# Sch_front.net
KiCad netlist of a schematic drawn in Altium Designer
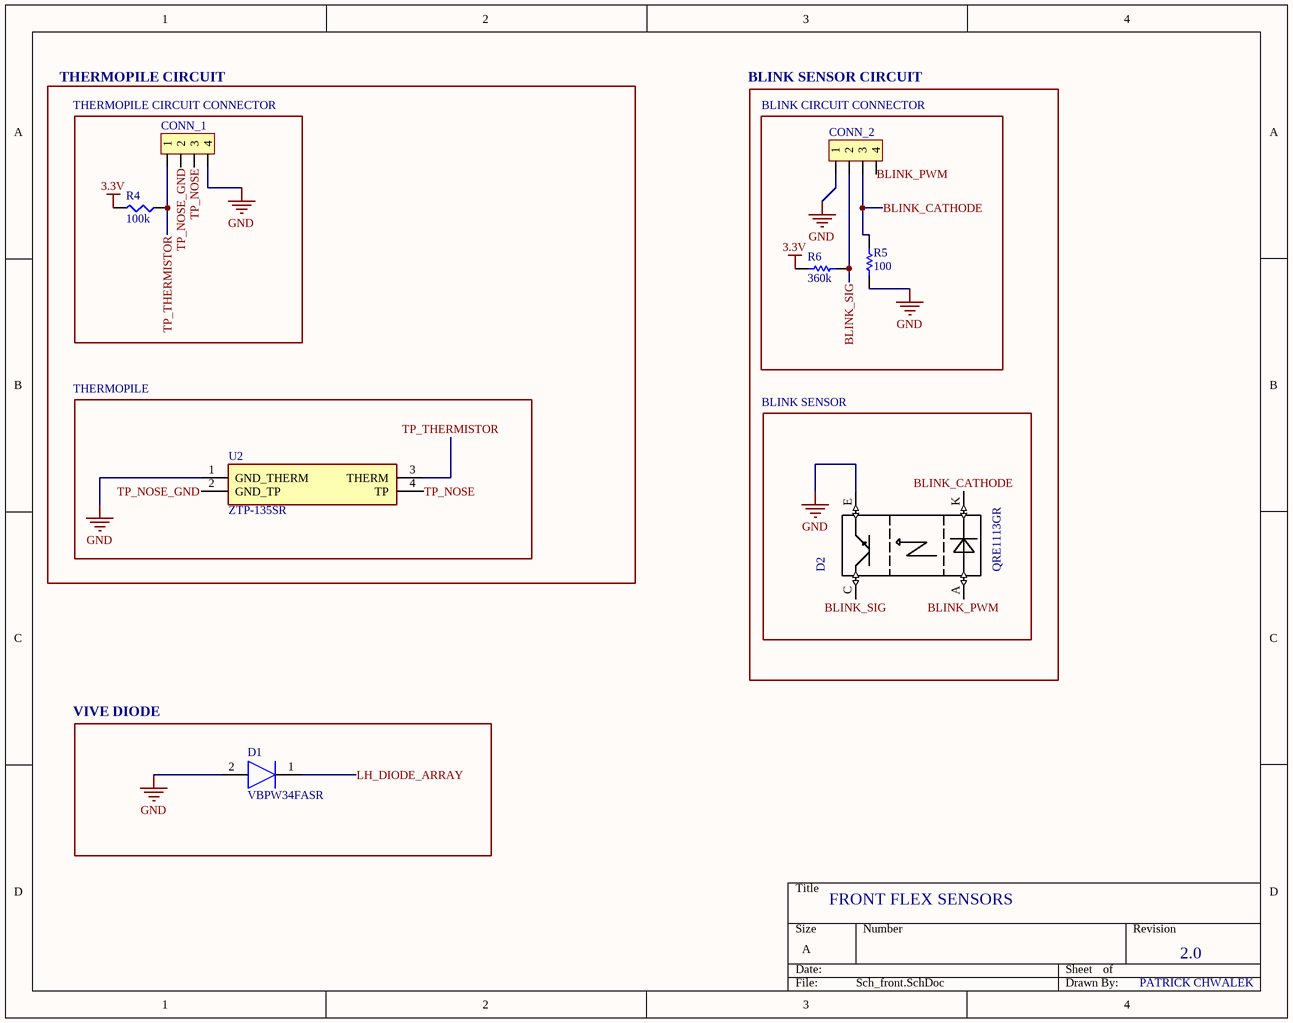
[diagram p0: Sch_front.SchDoc]

(export (version "E")
  (design (tool "Eeschema 10.0.6"))
  (components
    (comp (ref "CONN_1")
      (value "THERMO")
      (footprint "4_pos_1mm_header")
      (libsource (lib "schematic_components") (part "4_pin_1mm_header"))
    )
    (comp (ref "CONN_2")
      (value "BLINK")
      (footprint "4_pos_1mm_header")
      (libsource (lib "schematic_components") (part "4_pin_1mm_header"))
    )
    (comp (ref "D1")
      (value "VBPW34FASR")
      (footprint "VBPW34FAS")
      (description "Diode")
      (fields (field (name "MOUSER PART NUMBER") "782-VBPW34FASR") (field (name "RS PART NUMBER") "7689401"))
      (libsource (lib "*") (part "VBPW34FASR"))
    )
    (comp (ref "D2")
      (value "QRE1113GR")
      (footprint "*4LEADSMD_QRE1113GR(Primary)")
      (description "QRE1113 Series 30 V 50 mA Miniature Reflective Object Sensor - SMD-4")
      (fields (field (name "MF") "ON Semiconductor"))
      (libsource (lib "QRE1113GR") (part "QRE1113GR"))
    )
    (comp (ref "R4")
      (value "100k")
      (footprint "SMD-0402-RES")
      (description "RES SMD 100K OHM 5% 1/10W 0402")
      (fields (field (name "PART NUMBER") "ERJ-2GEJ104X") (field (name "DIGI-KEY PART NUMBER") "P100KJCT-ND"))
      (libsource (lib "Panasonic_ERJ_0402") (part "ERJ-2GEJ104X"))
    )
    (comp (ref "R5") (value "100") (footprint "0402R") (libsource (lib "bdm") (part "Resistor")))
    (comp (ref "R6")
      (value "360k")
      (footprint "0402R")
      (description "RC0402FR-07360KL")
      (libsource (lib "bdm") (part "Resistor"))
    )
    (comp (ref "U2")
      (value "ZTP-135SR")
      (footprint "ZTP-135SR")
      (description "Undefined or Miscellaneous")
      (fields (field (name "MOUSER PART NUMBER") "527-ZTP-135SR"))
      (libsource (lib "SamacSys") (part "ZTP-135SR"))
    )
  )
  (nets
    (net (code "1") (name "/BLINK_CATHODE") (class "Default")
      (node (ref "CONN_2") (pin "3") (pinfunction "3_3") (pintype "passive"))
      (node (ref "D2") (pin "K") (pinfunction "K_K") (pintype "bidirectional"))
      (node (ref "R5") (pin "2") (pinfunction "2_2") (pintype "passive"))
    )
    (net (code "2") (name "/BLINK_PWM") (class "Default")
      (node (ref "CONN_2") (pin "4") (pinfunction "4_4") (pintype "passive"))
      (node (ref "D2") (pin "A") (pinfunction "A_A") (pintype "bidirectional"))
    )
    (net (code "3") (name "/BLINK_SIG") (class "Default")
      (node (ref "CONN_2") (pin "2") (pinfunction "2_2") (pintype "passive"))
      (node (ref "D2") (pin "C") (pinfunction "C_C") (pintype "bidirectional"))
      (node (ref "R6") (pin "1") (pinfunction "1_1") (pintype "passive"))
    )
    (net (code "4") (name "/LH_DIODE_ARRAY") (class "Default")
      (node (ref "D1") (pin "1") (pinfunction "A_1") (pintype "passive"))
    )
    (net (code "5") (name "/TP_NOSE") (class "Default")
      (node (ref "CONN_1") (pin "3") (pinfunction "3_3") (pintype "passive"))
      (node (ref "U2") (pin "4") (pinfunction "TP_4") (pintype "passive"))
    )
    (net (code "6") (name "/TP_NOSE_GND") (class "Default")
      (node (ref "CONN_1") (pin "2") (pinfunction "2_2") (pintype "passive"))
      (node (ref "U2") (pin "2") (pinfunction "GND_TP_2") (pintype "passive"))
    )
    (net (code "7") (name "/TP_THERMISTOR") (class "Default")
      (node (ref "CONN_1") (pin "1") (pinfunction "1_1") (pintype "passive"))
      (node (ref "R4") (pin "1") (pinfunction "1_1") (pintype "passive"))
      (node (ref "U2") (pin "3") (pinfunction "THERM_3") (pintype "passive"))
    )
    (net (code "8") (name "3.3V") (class "Default")
      (node (ref "R4") (pin "2") (pinfunction "2_2") (pintype "passive"))
      (node (ref "R6") (pin "2") (pinfunction "2_2") (pintype "passive"))
    )
    (net (code "9") (name "GND") (class "Default")
      (node (ref "CONN_1") (pin "4") (pinfunction "4_4") (pintype "passive"))
      (node (ref "CONN_2") (pin "1") (pinfunction "1_1") (pintype "passive"))
      (node (ref "D1") (pin "2") (pinfunction "K_2") (pintype "passive"))
      (node (ref "D2") (pin "E") (pinfunction "E_E") (pintype "bidirectional"))
      (node (ref "R5") (pin "1") (pinfunction "1_1") (pintype "passive"))
      (node (ref "U2") (pin "1") (pinfunction "GND_THERM_1") (pintype "passive"))
    )
  )
)
